# Low_Side_Drivers.net
KiCad netlist of a schematic drawn in Altium Designer
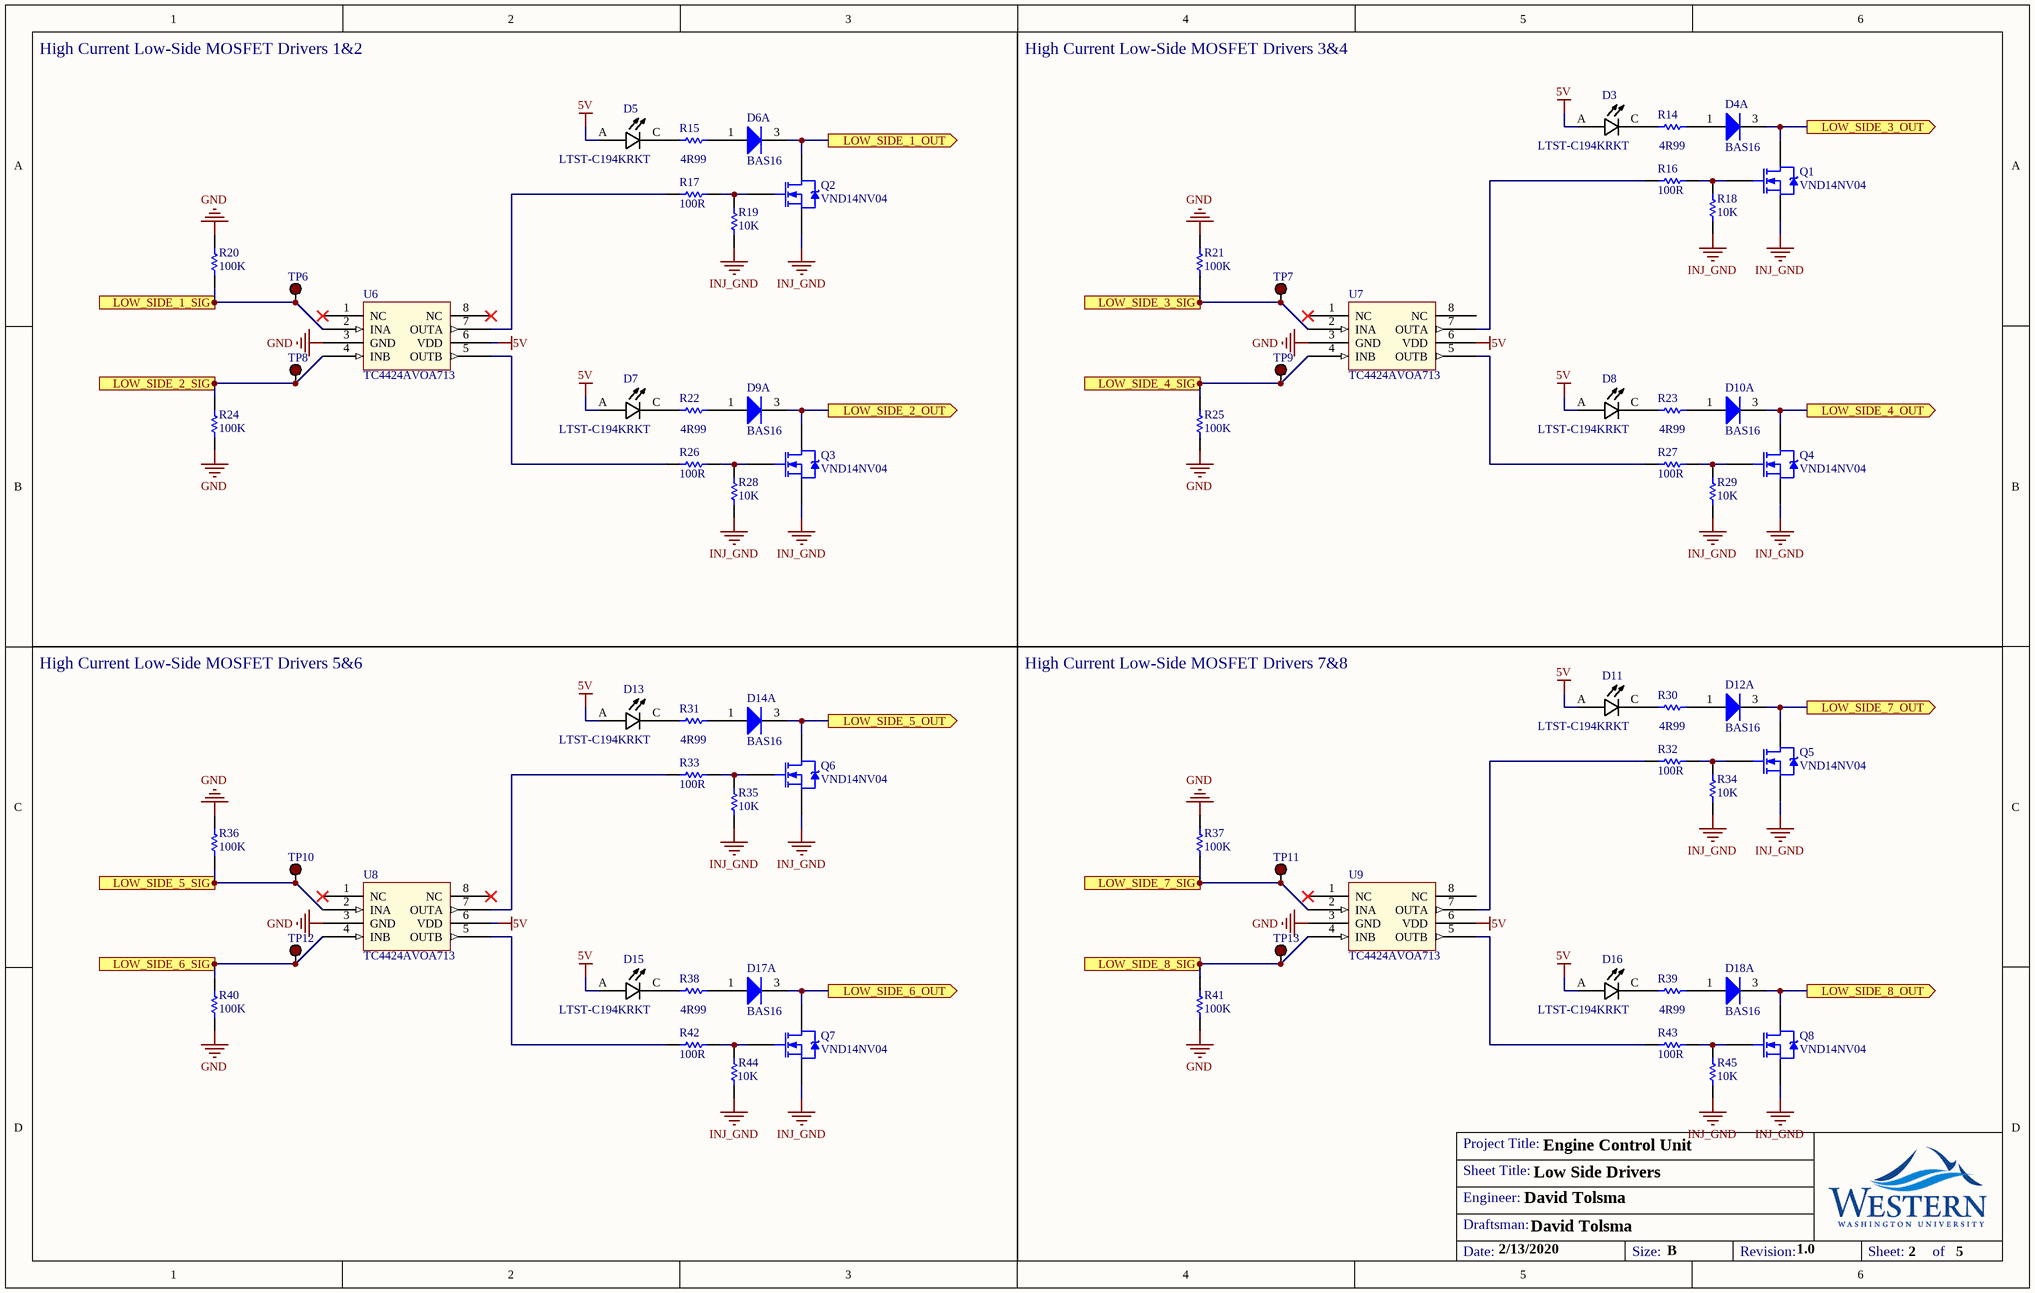
[diagram p0: Low_Side_Drivers.SchDoc]

(export (version "E")
  (design (tool "Eeschema 10.0.6"))
  (components
    (comp (ref "D3")
      (value "LTST-C194KRKT")
      (footprint "LEDC1608X35N_LTST-C194KRKT")
      (description "Red 631nm LED Indication - Discrete 2V 0603 _1608 Metric_")
      (fields (field (name "MF") "Lite-On Inc.") (field (name "DIGI-KEY_PART_NUMBER") "160-1835-1-ND"))
      (libsource (lib "ECU") (part "LTST-C194KRKT"))
    )
    (comp (ref "D4")
      (value "BAS16")
      (footprint "NXP-SOT23-3_V")
      (description "High-speed Switching Diode, 100 V, 4 ns, -65 to 150 degC, 3-Pin SOT23, RoHS, Tape and Reel")
      (fields (field (name "MANUFACTURER") "NXP Semiconductors"))
      (libsource (lib "Altium Content Vault") (part "NXP-D-A1K3-3"))
    )
    (comp (ref "D5")
      (value "LTST-C194KRKT")
      (footprint "LEDC1608X35N_LTST-C194KRKT")
      (description "Red 631nm LED Indication - Discrete 2V 0603 _1608 Metric_")
      (fields (field (name "MF") "Lite-On Inc.") (field (name "DIGI-KEY_PART_NUMBER") "160-1835-1-ND"))
      (libsource (lib "ECU") (part "LTST-C194KRKT"))
    )
    (comp (ref "D6")
      (value "BAS16")
      (footprint "NXP-SOT23-3_V")
      (description "High-speed Switching Diode, 100 V, 4 ns, -65 to 150 degC, 3-Pin SOT23, RoHS, Tape and Reel")
      (fields (field (name "MANUFACTURER") "NXP Semiconductors"))
      (libsource (lib "Altium Content Vault") (part "NXP-D-A1K3-3"))
    )
    (comp (ref "D7")
      (value "LTST-C194KRKT")
      (footprint "LEDC1608X35N_LTST-C194KRKT")
      (description "Red 631nm LED Indication - Discrete 2V 0603 _1608 Metric_")
      (fields (field (name "MF") "Lite-On Inc.") (field (name "DIGI-KEY_PART_NUMBER") "160-1835-1-ND"))
      (libsource (lib "ECU") (part "LTST-C194KRKT"))
    )
    (comp (ref "D8")
      (value "LTST-C194KRKT")
      (footprint "LEDC1608X35N_LTST-C194KRKT")
      (description "Red 631nm LED Indication - Discrete 2V 0603 _1608 Metric_")
      (fields (field (name "MF") "Lite-On Inc.") (field (name "DIGI-KEY_PART_NUMBER") "160-1835-1-ND"))
      (libsource (lib "ECU") (part "LTST-C194KRKT"))
    )
    (comp (ref "D9")
      (value "BAS16")
      (footprint "NXP-SOT23-3_V")
      (description "High-speed Switching Diode, 100 V, 4 ns, -65 to 150 degC, 3-Pin SOT23, RoHS, Tape and Reel")
      (fields (field (name "MANUFACTURER") "NXP Semiconductors"))
      (libsource (lib "Altium Content Vault") (part "NXP-D-A1K3-3"))
    )
    (comp (ref "D10")
      (value "BAS16")
      (footprint "NXP-SOT23-3_V")
      (description "High-speed Switching Diode, 100 V, 4 ns, -65 to 150 degC, 3-Pin SOT23, RoHS, Tape and Reel")
      (fields (field (name "MANUFACTURER") "NXP Semiconductors"))
      (libsource (lib "Altium Content Vault") (part "NXP-D-A1K3-3"))
    )
    (comp (ref "D11")
      (value "LTST-C194KRKT")
      (footprint "LEDC1608X35N_LTST-C194KRKT")
      (description "Red 631nm LED Indication - Discrete 2V 0603 _1608 Metric_")
      (fields (field (name "MF") "Lite-On Inc.") (field (name "DIGI-KEY_PART_NUMBER") "160-1835-1-ND"))
      (libsource (lib "ECU") (part "LTST-C194KRKT"))
    )
    (comp (ref "D12")
      (value "BAS16")
      (footprint "NXP-SOT23-3_V")
      (description "High-speed Switching Diode, 100 V, 4 ns, -65 to 150 degC, 3-Pin SOT23, RoHS, Tape and Reel")
      (fields (field (name "MANUFACTURER") "NXP Semiconductors"))
      (libsource (lib "Altium Content Vault") (part "NXP-D-A1K3-3"))
    )
    (comp (ref "D13")
      (value "LTST-C194KRKT")
      (footprint "LEDC1608X35N_LTST-C194KRKT")
      (description "Red 631nm LED Indication - Discrete 2V 0603 _1608 Metric_")
      (fields (field (name "MF") "Lite-On Inc.") (field (name "DIGI-KEY_PART_NUMBER") "160-1835-1-ND"))
      (libsource (lib "ECU") (part "LTST-C194KRKT"))
    )
    (comp (ref "D14")
      (value "BAS16")
      (footprint "NXP-SOT23-3_V")
      (description "High-speed Switching Diode, 100 V, 4 ns, -65 to 150 degC, 3-Pin SOT23, RoHS, Tape and Reel")
      (fields (field (name "MANUFACTURER") "NXP Semiconductors"))
      (libsource (lib "Altium Content Vault") (part "NXP-D-A1K3-3"))
    )
    (comp (ref "D15")
      (value "LTST-C194KRKT")
      (footprint "LEDC1608X35N_LTST-C194KRKT")
      (description "Red 631nm LED Indication - Discrete 2V 0603 _1608 Metric_")
      (fields (field (name "MF") "Lite-On Inc.") (field (name "DIGI-KEY_PART_NUMBER") "160-1835-1-ND"))
      (libsource (lib "ECU") (part "LTST-C194KRKT"))
    )
    (comp (ref "D16")
      (value "LTST-C194KRKT")
      (footprint "LEDC1608X35N_LTST-C194KRKT")
      (description "Red 631nm LED Indication - Discrete 2V 0603 _1608 Metric_")
      (fields (field (name "MF") "Lite-On Inc.") (field (name "DIGI-KEY_PART_NUMBER") "160-1835-1-ND"))
      (libsource (lib "ECU") (part "LTST-C194KRKT"))
    )
    (comp (ref "D17")
      (value "BAS16")
      (footprint "NXP-SOT23-3_V")
      (description "High-speed Switching Diode, 100 V, 4 ns, -65 to 150 degC, 3-Pin SOT23, RoHS, Tape and Reel")
      (fields (field (name "MANUFACTURER") "NXP Semiconductors"))
      (libsource (lib "Altium Content Vault") (part "NXP-D-A1K3-3"))
    )
    (comp (ref "D18")
      (value "BAS16")
      (footprint "NXP-SOT23-3_V")
      (description "High-speed Switching Diode, 100 V, 4 ns, -65 to 150 degC, 3-Pin SOT23, RoHS, Tape and Reel")
      (fields (field (name "MANUFACTURER") "NXP Semiconductors"))
      (libsource (lib "Altium Content Vault") (part "NXP-D-A1K3-3"))
    )
    (comp (ref "Q1") (value "VND14NV04") (footprint "VND14NV04") (libsource (lib "ECU") (part "VND14NV04")))
    (comp (ref "Q2") (value "VND14NV04") (footprint "VND14NV04") (libsource (lib "ECU") (part "VND14NV04")))
    (comp (ref "Q3") (value "VND14NV04") (footprint "VND14NV04") (libsource (lib "ECU") (part "VND14NV04")))
    (comp (ref "Q4") (value "VND14NV04") (footprint "VND14NV04") (libsource (lib "ECU") (part "VND14NV04")))
    (comp (ref "Q5") (value "VND14NV04") (footprint "VND14NV04") (libsource (lib "ECU") (part "VND14NV04")))
    (comp (ref "Q6") (value "VND14NV04") (footprint "VND14NV04") (libsource (lib "ECU") (part "VND14NV04")))
    (comp (ref "Q7") (value "VND14NV04") (footprint "VND14NV04") (libsource (lib "ECU") (part "VND14NV04")))
    (comp (ref "Q8") (value "VND14NV04") (footprint "VND14NV04") (libsource (lib "ECU") (part "VND14NV04")))
    (comp (ref "R14")
      (value "4R99")
      (footprint "RESC0603(1608)_M")
      (description "4R99 0.1W 1% 0603 (1608 Metric)  SMD")
      (fields (field (name "TOLERANCE") "1 %") (field (name "POWER") "0.1 W"))
      (libsource (lib "Altium Content Vault") (part "RES"))
    )
    (comp (ref "R15")
      (value "4R99")
      (footprint "RESC0603(1608)_M")
      (description "4R99 0.1W 1% 0603 (1608 Metric)  SMD")
      (fields (field (name "TOLERANCE") "1 %") (field (name "POWER") "0.1 W"))
      (libsource (lib "Altium Content Vault") (part "RES"))
    )
    (comp (ref "R16")
      (value "100R")
      (footprint "RESC1206(3216)_L")
      (description "100R 0.25W 1% 1206 (3216 Metric)  SMD")
      (fields (field (name "TOLERANCE") "1 %") (field (name "POWER") "0.25 W"))
      (libsource (lib "Altium Content Vault") (part "RES"))
    )
    (comp (ref "R17")
      (value "100R")
      (footprint "RESC1206(3216)_L")
      (description "100R 0.25W 1% 1206 (3216 Metric)  SMD")
      (fields (field (name "TOLERANCE") "1 %") (field (name "POWER") "0.25 W"))
      (libsource (lib "Altium Content Vault") (part "RES"))
    )
    (comp (ref "R18")
      (value "10K")
      (footprint "RESC0603(1608)_M")
      (description "10K 0.1W 1% 0603 (1608 Metric)  SMD")
      (fields (field (name "POWER") "0.1 W") (field (name "TOLERANCE") "1 %"))
      (libsource (lib "Altium Content Vault") (part "RES"))
    )
    (comp (ref "R19")
      (value "10K")
      (footprint "RESC0603(1608)_M")
      (description "10K 0.1W 1% 0603 (1608 Metric)  SMD")
      (fields (field (name "POWER") "0.1 W") (field (name "TOLERANCE") "1 %"))
      (libsource (lib "Altium Content Vault") (part "RES"))
    )
    (comp (ref "R20")
      (value "100K")
      (footprint "RESC0603(1608)_M")
      (description "100K 0.1W 1% 0603 (1608 Metric)  SMD")
      (fields (field (name "POWER") "0.1 W") (field (name "TOLERANCE") "1 %"))
      (libsource (lib "Altium Content Vault") (part "RES"))
    )
    (comp (ref "R21")
      (value "100K")
      (footprint "RESC0603(1608)_M")
      (description "100K 0.1W 1% 0603 (1608 Metric)  SMD")
      (fields (field (name "POWER") "0.1 W") (field (name "TOLERANCE") "1 %"))
      (libsource (lib "Altium Content Vault") (part "RES"))
    )
    (comp (ref "R22")
      (value "4R99")
      (footprint "RESC0603(1608)_M")
      (description "4R99 0.1W 1% 0603 (1608 Metric)  SMD")
      (fields (field (name "TOLERANCE") "1 %") (field (name "POWER") "0.1 W"))
      (libsource (lib "Altium Content Vault") (part "RES"))
    )
    (comp (ref "R23")
      (value "4R99")
      (footprint "RESC0603(1608)_M")
      (description "4R99 0.1W 1% 0603 (1608 Metric)  SMD")
      (fields (field (name "TOLERANCE") "1 %") (field (name "POWER") "0.1 W"))
      (libsource (lib "Altium Content Vault") (part "RES"))
    )
    (comp (ref "R24")
      (value "100K")
      (footprint "RESC0603(1608)_M")
      (description "100K 0.1W 1% 0603 (1608 Metric)  SMD")
      (fields (field (name "POWER") "0.1 W") (field (name "TOLERANCE") "1 %"))
      (libsource (lib "Altium Content Vault") (part "RES"))
    )
    (comp (ref "R25")
      (value "100K")
      (footprint "RESC0603(1608)_M")
      (description "100K 0.1W 1% 0603 (1608 Metric)  SMD")
      (fields (field (name "POWER") "0.1 W") (field (name "TOLERANCE") "1 %"))
      (libsource (lib "Altium Content Vault") (part "RES"))
    )
    (comp (ref "R26")
      (value "100R")
      (footprint "RESC1206(3216)_L")
      (description "100R 0.25W 1% 1206 (3216 Metric)  SMD")
      (fields (field (name "TOLERANCE") "1 %") (field (name "POWER") "0.25 W"))
      (libsource (lib "Altium Content Vault") (part "RES"))
    )
    (comp (ref "R27")
      (value "100R")
      (footprint "RESC1206(3216)_L")
      (description "100R 0.25W 1% 1206 (3216 Metric)  SMD")
      (fields (field (name "TOLERANCE") "1 %") (field (name "POWER") "0.25 W"))
      (libsource (lib "Altium Content Vault") (part "RES"))
    )
    (comp (ref "R28")
      (value "10K")
      (footprint "RESC0603(1608)_M")
      (description "10K 0.1W 1% 0603 (1608 Metric)  SMD")
      (fields (field (name "POWER") "0.1 W") (field (name "TOLERANCE") "1 %"))
      (libsource (lib "Altium Content Vault") (part "RES"))
    )
    (comp (ref "R29")
      (value "10K")
      (footprint "RESC0603(1608)_M")
      (description "10K 0.1W 1% 0603 (1608 Metric)  SMD")
      (fields (field (name "POWER") "0.1 W") (field (name "TOLERANCE") "1 %"))
      (libsource (lib "Altium Content Vault") (part "RES"))
    )
    (comp (ref "R30")
      (value "4R99")
      (footprint "RESC0603(1608)_M")
      (description "4R99 0.1W 1% 0603 (1608 Metric)  SMD")
      (fields (field (name "TOLERANCE") "1 %") (field (name "POWER") "0.1 W"))
      (libsource (lib "Altium Content Vault") (part "RES"))
    )
    (comp (ref "R31")
      (value "4R99")
      (footprint "RESC0603(1608)_M")
      (description "4R99 0.1W 1% 0603 (1608 Metric)  SMD")
      (fields (field (name "TOLERANCE") "1 %") (field (name "POWER") "0.1 W"))
      (libsource (lib "Altium Content Vault") (part "RES"))
    )
    (comp (ref "R32")
      (value "100R")
      (footprint "RESC1206(3216)_L")
      (description "100R 0.25W 1% 1206 (3216 Metric)  SMD")
      (fields (field (name "TOLERANCE") "1 %") (field (name "POWER") "0.25 W"))
      (libsource (lib "Altium Content Vault") (part "RES"))
    )
    (comp (ref "R33")
      (value "100R")
      (footprint "RESC1206(3216)_L")
      (description "100R 0.25W 1% 1206 (3216 Metric)  SMD")
      (fields (field (name "TOLERANCE") "1 %") (field (name "POWER") "0.25 W"))
      (libsource (lib "Altium Content Vault") (part "RES"))
    )
    (comp (ref "R34")
      (value "10K")
      (footprint "RESC0603(1608)_M")
      (description "10K 0.1W 1% 0603 (1608 Metric)  SMD")
      (fields (field (name "POWER") "0.1 W") (field (name "TOLERANCE") "1 %"))
      (libsource (lib "Altium Content Vault") (part "RES"))
    )
    (comp (ref "R35")
      (value "10K")
      (footprint "RESC0603(1608)_M")
      (description "10K 0.1W 1% 0603 (1608 Metric)  SMD")
      (fields (field (name "POWER") "0.1 W") (field (name "TOLERANCE") "1 %"))
      (libsource (lib "Altium Content Vault") (part "RES"))
    )
    (comp (ref "R36")
      (value "100K")
      (footprint "RESC0603(1608)_M")
      (description "100K 0.1W 1% 0603 (1608 Metric)  SMD")
      (fields (field (name "POWER") "0.1 W") (field (name "TOLERANCE") "1 %"))
      (libsource (lib "Altium Content Vault") (part "RES"))
    )
    (comp (ref "R37")
      (value "100K")
      (footprint "RESC0603(1608)_M")
      (description "100K 0.1W 1% 0603 (1608 Metric)  SMD")
      (fields (field (name "POWER") "0.1 W") (field (name "TOLERANCE") "1 %"))
      (libsource (lib "Altium Content Vault") (part "RES"))
    )
    (comp (ref "R38")
      (value "4R99")
      (footprint "RESC0603(1608)_M")
      (description "4R99 0.1W 1% 0603 (1608 Metric)  SMD")
      (fields (field (name "TOLERANCE") "1 %") (field (name "POWER") "0.1 W"))
      (libsource (lib "Altium Content Vault") (part "RES"))
    )
    (comp (ref "R39")
      (value "4R99")
      (footprint "RESC0603(1608)_M")
      (description "4R99 0.1W 1% 0603 (1608 Metric)  SMD")
      (fields (field (name "TOLERANCE") "1 %") (field (name "POWER") "0.1 W"))
      (libsource (lib "Altium Content Vault") (part "RES"))
    )
    (comp (ref "R40")
      (value "100K")
      (footprint "RESC0603(1608)_M")
      (description "100K 0.1W 1% 0603 (1608 Metric)  SMD")
      (fields (field (name "POWER") "0.1 W") (field (name "TOLERANCE") "1 %"))
      (libsource (lib "Altium Content Vault") (part "RES"))
    )
    (comp (ref "R41")
      (value "100K")
      (footprint "RESC0603(1608)_M")
      (description "100K 0.1W 1% 0603 (1608 Metric)  SMD")
      (fields (field (name "POWER") "0.1 W") (field (name "TOLERANCE") "1 %"))
      (libsource (lib "Altium Content Vault") (part "RES"))
    )
    (comp (ref "R42")
      (value "100R")
      (footprint "RESC1206(3216)_L")
      (description "100R 0.25W 1% 1206 (3216 Metric)  SMD")
      (fields (field (name "TOLERANCE") "1 %") (field (name "POWER") "0.25 W"))
      (libsource (lib "Altium Content Vault") (part "RES"))
    )
    (comp (ref "R43")
      (value "100R")
      (footprint "RESC1206(3216)_L")
      (description "100R 0.25W 1% 1206 (3216 Metric)  SMD")
      (fields (field (name "TOLERANCE") "1 %") (field (name "POWER") "0.25 W"))
      (libsource (lib "Altium Content Vault") (part "RES"))
    )
    (comp (ref "R44")
      (value "10K")
      (footprint "RESC0603(1608)_M")
      (description "10K 0.1W 1% 0603 (1608 Metric)  SMD")
      (fields (field (name "POWER") "0.1 W") (field (name "TOLERANCE") "1 %"))
      (libsource (lib "Altium Content Vault") (part "RES"))
    )
    (comp (ref "R45")
      (value "10K")
      (footprint "RESC0603(1608)_M")
      (description "10K 0.1W 1% 0603 (1608 Metric)  SMD")
      (fields (field (name "POWER") "0.1 W") (field (name "TOLERANCE") "1 %"))
      (libsource (lib "Altium Content Vault") (part "RES"))
    )
    (comp (ref "TP6")
      (value "5001")
      (footprint "Keystone_5001")
      (description "TEST POINT PC MINI .040\"D BLACK")
      (fields (field (name "MANUFACTURER") "Keystone Electronics"))
      (libsource (lib "WWUEE_SchematicLibrary") (part "TEST POINT"))
    )
    (comp (ref "TP7")
      (value "5001")
      (footprint "Keystone_5001")
      (description "TEST POINT PC MINI .040\"D BLACK")
      (fields (field (name "MANUFACTURER") "Keystone Electronics"))
      (libsource (lib "WWUEE_SchematicLibrary") (part "TEST POINT"))
    )
    (comp (ref "TP8")
      (value "5001")
      (footprint "Keystone_5001")
      (description "TEST POINT PC MINI .040\"D BLACK")
      (fields (field (name "MANUFACTURER") "Keystone Electronics"))
      (libsource (lib "WWUEE_SchematicLibrary") (part "TEST POINT"))
    )
    (comp (ref "TP9")
      (value "5001")
      (footprint "Keystone_5001")
      (description "TEST POINT PC MINI .040\"D BLACK")
      (fields (field (name "MANUFACTURER") "Keystone Electronics"))
      (libsource (lib "WWUEE_SchematicLibrary") (part "TEST POINT"))
    )
    (comp (ref "TP10")
      (value "5001")
      (footprint "Keystone_5001")
      (description "TEST POINT PC MINI .040\"D BLACK")
      (fields (field (name "MANUFACTURER") "Keystone Electronics"))
      (libsource (lib "WWUEE_SchematicLibrary") (part "TEST POINT"))
    )
    (comp (ref "TP11")
      (value "5001")
      (footprint "Keystone_5001")
      (description "TEST POINT PC MINI .040\"D BLACK")
      (fields (field (name "MANUFACTURER") "Keystone Electronics"))
      (libsource (lib "WWUEE_SchematicLibrary") (part "TEST POINT"))
    )
    (comp (ref "TP12")
      (value "5001")
      (footprint "Keystone_5001")
      (description "TEST POINT PC MINI .040\"D BLACK")
      (fields (field (name "MANUFACTURER") "Keystone Electronics"))
      (libsource (lib "WWUEE_SchematicLibrary") (part "TEST POINT"))
    )
    (comp (ref "TP13")
      (value "5001")
      (footprint "Keystone_5001")
      (description "TEST POINT PC MINI .040\"D BLACK")
      (fields (field (name "MANUFACTURER") "Keystone Electronics"))
      (libsource (lib "WWUEE_SchematicLibrary") (part "TEST POINT"))
    )
    (comp (ref "U6")
      (value "TC4424AVOA713")
      (footprint "TC4424AVOA713")
      (libsource (lib "ECU") (part "TC4424AVOA713"))
    )
    (comp (ref "U7")
      (value "TC4424AVOA713")
      (footprint "TC4424AVOA713")
      (libsource (lib "ECU") (part "TC4424AVOA713"))
    )
    (comp (ref "U8")
      (value "TC4424AVOA713")
      (footprint "TC4424AVOA713")
      (libsource (lib "ECU") (part "TC4424AVOA713"))
    )
    (comp (ref "U9")
      (value "TC4424AVOA713")
      (footprint "TC4424AVOA713")
      (libsource (lib "ECU") (part "TC4424AVOA713"))
    )
  )
  (nets
    (net (code "1") (name "/LOW_SIDE_1_OUT") (class "Default")
      (node (ref "D6") (pin "3") (pinfunction "K_3") (pintype "passive"))
      (node (ref "Q2") (pin "4") (pinfunction "D_4") (pintype "passive"))
    )
    (net (code "2") (name "/LOW_SIDE_1_SIG") (class "Default")
      (node (ref "R20") (pin "2") (pinfunction "2_2") (pintype "passive"))
      (node (ref "TP6") (pin "1") (pinfunction "TP_1") (pintype "passive"))
      (node (ref "U6") (pin "2") (pinfunction "INA_2") (pintype "input"))
    )
    (net (code "3") (name "/LOW_SIDE_2_OUT") (class "Default")
      (node (ref "D9") (pin "3") (pinfunction "K_3") (pintype "passive"))
      (node (ref "Q3") (pin "4") (pinfunction "D_4") (pintype "passive"))
    )
    (net (code "4") (name "/LOW_SIDE_2_SIG") (class "Default")
      (node (ref "R24") (pin "2") (pinfunction "2_2") (pintype "passive"))
      (node (ref "TP8") (pin "1") (pinfunction "TP_1") (pintype "passive"))
      (node (ref "U6") (pin "4") (pinfunction "INB_4") (pintype "input"))
    )
    (net (code "5") (name "/LOW_SIDE_3_OUT") (class "Default")
      (node (ref "D4") (pin "3") (pinfunction "K_3") (pintype "passive"))
      (node (ref "Q1") (pin "4") (pinfunction "D_4") (pintype "passive"))
    )
    (net (code "6") (name "/LOW_SIDE_3_SIG") (class "Default")
      (node (ref "R21") (pin "2") (pinfunction "2_2") (pintype "passive"))
      (node (ref "TP7") (pin "1") (pinfunction "TP_1") (pintype "passive"))
      (node (ref "U7") (pin "2") (pinfunction "INA_2") (pintype "input"))
    )
    (net (code "7") (name "/LOW_SIDE_4_OUT") (class "Default")
      (node (ref "D10") (pin "3") (pinfunction "K_3") (pintype "passive"))
      (node (ref "Q4") (pin "4") (pinfunction "D_4") (pintype "passive"))
    )
    (net (code "8") (name "/LOW_SIDE_4_SIG") (class "Default")
      (node (ref "R25") (pin "2") (pinfunction "2_2") (pintype "passive"))
      (node (ref "TP9") (pin "1") (pinfunction "TP_1") (pintype "passive"))
      (node (ref "U7") (pin "4") (pinfunction "INB_4") (pintype "input"))
    )
    (net (code "9") (name "/LOW_SIDE_5_OUT") (class "Default")
      (node (ref "D14") (pin "3") (pinfunction "K_3") (pintype "passive"))
      (node (ref "Q6") (pin "4") (pinfunction "D_4") (pintype "passive"))
    )
    (net (code "10") (name "/LOW_SIDE_5_SIG") (class "Default")
      (node (ref "R36") (pin "2") (pinfunction "2_2") (pintype "passive"))
      (node (ref "TP10") (pin "1") (pinfunction "TP_1") (pintype "passive"))
      (node (ref "U8") (pin "2") (pinfunction "INA_2") (pintype "input"))
    )
    (net (code "11") (name "/LOW_SIDE_6_OUT") (class "Default")
      (node (ref "D17") (pin "3") (pinfunction "K_3") (pintype "passive"))
      (node (ref "Q7") (pin "4") (pinfunction "D_4") (pintype "passive"))
    )
    (net (code "12") (name "/LOW_SIDE_6_SIG") (class "Default")
      (node (ref "R40") (pin "2") (pinfunction "2_2") (pintype "passive"))
      (node (ref "TP12") (pin "1") (pinfunction "TP_1") (pintype "passive"))
      (node (ref "U8") (pin "4") (pinfunction "INB_4") (pintype "input"))
    )
    (net (code "13") (name "/LOW_SIDE_7_OUT") (class "Default")
      (node (ref "D12") (pin "3") (pinfunction "K_3") (pintype "passive"))
      (node (ref "Q5") (pin "4") (pinfunction "D_4") (pintype "passive"))
    )
    (net (code "14") (name "/LOW_SIDE_7_SIG") (class "Default")
      (node (ref "R37") (pin "2") (pinfunction "2_2") (pintype "passive"))
      (node (ref "TP11") (pin "1") (pinfunction "TP_1") (pintype "passive"))
      (node (ref "U9") (pin "2") (pinfunction "INA_2") (pintype "input"))
    )
    (net (code "15") (name "/LOW_SIDE_8_OUT") (class "Default")
      (node (ref "D18") (pin "3") (pinfunction "K_3") (pintype "passive"))
      (node (ref "Q8") (pin "4") (pinfunction "D_4") (pintype "passive"))
    )
    (net (code "16") (name "/LOW_SIDE_8_SIG") (class "Default")
      (node (ref "R41") (pin "2") (pinfunction "2_2") (pintype "passive"))
      (node (ref "TP13") (pin "1") (pinfunction "TP_1") (pintype "passive"))
      (node (ref "U9") (pin "4") (pinfunction "INB_4") (pintype "input"))
    )
    (net (code "17") (name "5V") (class "Default")
      (node (ref "D11") (pin "A") (pinfunction "A_A") (pintype "passive"))
      (node (ref "D13") (pin "A") (pinfunction "A_A") (pintype "passive"))
      (node (ref "D15") (pin "A") (pinfunction "A_A") (pintype "passive"))
      (node (ref "D16") (pin "A") (pinfunction "A_A") (pintype "passive"))
      (node (ref "D3") (pin "A") (pinfunction "A_A") (pintype "passive"))
      (node (ref "D5") (pin "A") (pinfunction "A_A") (pintype "passive"))
      (node (ref "D7") (pin "A") (pinfunction "A_A") (pintype "passive"))
      (node (ref "D8") (pin "A") (pinfunction "A_A") (pintype "passive"))
      (node (ref "U6") (pin "6") (pinfunction "VDD_6") (pintype "power_in"))
      (node (ref "U7") (pin "6") (pinfunction "VDD_6") (pintype "power_in"))
      (node (ref "U8") (pin "6") (pinfunction "VDD_6") (pintype "power_in"))
      (node (ref "U9") (pin "6") (pinfunction "VDD_6") (pintype "power_in"))
    )
    (net (code "18") (name "GND") (class "Default")
      (node (ref "R20") (pin "1") (pinfunction "1_1") (pintype "passive"))
      (node (ref "R21") (pin "1") (pinfunction "1_1") (pintype "passive"))
      (node (ref "R24") (pin "1") (pinfunction "1_1") (pintype "passive"))
      (node (ref "R25") (pin "1") (pinfunction "1_1") (pintype "passive"))
      (node (ref "R36") (pin "1") (pinfunction "1_1") (pintype "passive"))
      (node (ref "R37") (pin "1") (pinfunction "1_1") (pintype "passive"))
      (node (ref "R40") (pin "1") (pinfunction "1_1") (pintype "passive"))
      (node (ref "R41") (pin "1") (pinfunction "1_1") (pintype "passive"))
      (node (ref "U6") (pin "3") (pinfunction "GND_3") (pintype "power_in"))
      (node (ref "U7") (pin "3") (pinfunction "GND_3") (pintype "power_in"))
      (node (ref "U8") (pin "3") (pinfunction "GND_3") (pintype "power_in"))
      (node (ref "U9") (pin "3") (pinfunction "GND_3") (pintype "power_in"))
    )
    (net (code "19") (name "INJ_GND") (class "Default")
      (node (ref "Q1") (pin "3") (pinfunction "S_3") (pintype "passive"))
      (node (ref "Q2") (pin "3") (pinfunction "S_3") (pintype "passive"))
      (node (ref "Q3") (pin "3") (pinfunction "S_3") (pintype "passive"))
      (node (ref "Q4") (pin "3") (pinfunction "S_3") (pintype "passive"))
      (node (ref "Q5") (pin "3") (pinfunction "S_3") (pintype "passive"))
      (node (ref "Q6") (pin "3") (pinfunction "S_3") (pintype "passive"))
      (node (ref "Q7") (pin "3") (pinfunction "S_3") (pintype "passive"))
      (node (ref "Q8") (pin "3") (pinfunction "S_3") (pintype "passive"))
      (node (ref "R18") (pin "1") (pinfunction "1_1") (pintype "passive"))
      (node (ref "R19") (pin "1") (pinfunction "1_1") (pintype "passive"))
      (node (ref "R28") (pin "1") (pinfunction "1_1") (pintype "passive"))
      (node (ref "R29") (pin "1") (pinfunction "1_1") (pintype "passive"))
      (node (ref "R34") (pin "1") (pinfunction "1_1") (pintype "passive"))
      (node (ref "R35") (pin "1") (pinfunction "1_1") (pintype "passive"))
      (node (ref "R44") (pin "1") (pinfunction "1_1") (pintype "passive"))
      (node (ref "R45") (pin "1") (pinfunction "1_1") (pintype "passive"))
    )
    (net (code "20") (name "Net-(D3-PadC)") (class "Default")
      (node (ref "D3") (pin "C") (pinfunction "C_C") (pintype "passive"))
      (node (ref "R14") (pin "1") (pinfunction "1_1") (pintype "passive"))
    )
    (net (code "21") (name "Net-(D4A-A)") (class "Default")
      (node (ref "D4") (pin "1") (pinfunction "A_1") (pintype "passive"))
      (node (ref "R14") (pin "2") (pinfunction "2_2") (pintype "passive"))
    )
    (net (code "22") (name "Net-(D5-PadC)") (class "Default")
      (node (ref "D5") (pin "C") (pinfunction "C_C") (pintype "passive"))
      (node (ref "R15") (pin "1") (pinfunction "1_1") (pintype "passive"))
    )
    (net (code "23") (name "Net-(D6A-A)") (class "Default")
      (node (ref "D6") (pin "1") (pinfunction "A_1") (pintype "passive"))
      (node (ref "R15") (pin "2") (pinfunction "2_2") (pintype "passive"))
    )
    (net (code "24") (name "Net-(D7-PadC)") (class "Default")
      (node (ref "D7") (pin "C") (pinfunction "C_C") (pintype "passive"))
      (node (ref "R22") (pin "1") (pinfunction "1_1") (pintype "passive"))
    )
    (net (code "25") (name "Net-(D8-PadC)") (class "Default")
      (node (ref "D8") (pin "C") (pinfunction "C_C") (pintype "passive"))
      (node (ref "R23") (pin "1") (pinfunction "1_1") (pintype "passive"))
    )
    (net (code "26") (name "Net-(D9A-A)") (class "Default")
      (node (ref "D9") (pin "1") (pinfunction "A_1") (pintype "passive"))
      (node (ref "R22") (pin "2") (pinfunction "2_2") (pintype "passive"))
    )
    (net (code "27") (name "Net-(D10A-A)") (class "Default")
      (node (ref "D10") (pin "1") (pinfunction "A_1") (pintype "passive"))
      (node (ref "R23") (pin "2") (pinfunction "2_2") (pintype "passive"))
    )
    (net (code "28") (name "Net-(D11-PadC)") (class "Default")
      (node (ref "D11") (pin "C") (pinfunction "C_C") (pintype "passive"))
      (node (ref "R30") (pin "1") (pinfunction "1_1") (pintype "passive"))
    )
    (net (code "29") (name "Net-(D12A-A)") (class "Default")
      (node (ref "D12") (pin "1") (pinfunction "A_1") (pintype "passive"))
      (node (ref "R30") (pin "2") (pinfunction "2_2") (pintype "passive"))
    )
    (net (code "30") (name "Net-(D13-PadC)") (class "Default")
      (node (ref "D13") (pin "C") (pinfunction "C_C") (pintype "passive"))
      (node (ref "R31") (pin "1") (pinfunction "1_1") (pintype "passive"))
    )
    (net (code "31") (name "Net-(D14A-A)") (class "Default")
      (node (ref "D14") (pin "1") (pinfunction "A_1") (pintype "passive"))
      (node (ref "R31") (pin "2") (pinfunction "2_2") (pintype "passive"))
    )
    (net (code "32") (name "Net-(D15-PadC)") (class "Default")
      (node (ref "D15") (pin "C") (pinfunction "C_C") (pintype "passive"))
      (node (ref "R38") (pin "1") (pinfunction "1_1") (pintype "passive"))
    )
    (net (code "33") (name "Net-(D16-PadC)") (class "Default")
      (node (ref "D16") (pin "C") (pinfunction "C_C") (pintype "passive"))
      (node (ref "R39") (pin "1") (pinfunction "1_1") (pintype "passive"))
    )
    (net (code "34") (name "Net-(D17A-A)") (class "Default")
      (node (ref "D17") (pin "1") (pinfunction "A_1") (pintype "passive"))
      (node (ref "R38") (pin "2") (pinfunction "2_2") (pintype "passive"))
    )
    (net (code "35") (name "Net-(D18A-A)") (class "Default")
      (node (ref "D18") (pin "1") (pinfunction "A_1") (pintype "passive"))
      (node (ref "R39") (pin "2") (pinfunction "2_2") (pintype "passive"))
    )
    (net (code "36") (name "Net-(Q1-G)") (class "Default")
      (node (ref "Q1") (pin "1") (pinfunction "G_1") (pintype "passive"))
      (node (ref "R16") (pin "2") (pinfunction "2_2") (pintype "passive"))
      (node (ref "R18") (pin "2") (pinfunction "2_2") (pintype "passive"))
    )
    (net (code "37") (name "Net-(Q2-G)") (class "Default")
      (node (ref "Q2") (pin "1") (pinfunction "G_1") (pintype "passive"))
      (node (ref "R17") (pin "2") (pinfunction "2_2") (pintype "passive"))
      (node (ref "R19") (pin "2") (pinfunction "2_2") (pintype "passive"))
    )
    (net (code "38") (name "Net-(Q3-G)") (class "Default")
      (node (ref "Q3") (pin "1") (pinfunction "G_1") (pintype "passive"))
      (node (ref "R26") (pin "2") (pinfunction "2_2") (pintype "passive"))
      (node (ref "R28") (pin "2") (pinfunction "2_2") (pintype "passive"))
    )
    (net (code "39") (name "Net-(Q4-G)") (class "Default")
      (node (ref "Q4") (pin "1") (pinfunction "G_1") (pintype "passive"))
      (node (ref "R27") (pin "2") (pinfunction "2_2") (pintype "passive"))
      (node (ref "R29") (pin "2") (pinfunction "2_2") (pintype "passive"))
    )
    (net (code "40") (name "Net-(Q5-G)") (class "Default")
      (node (ref "Q5") (pin "1") (pinfunction "G_1") (pintype "passive"))
      (node (ref "R32") (pin "2") (pinfunction "2_2") (pintype "passive"))
      (node (ref "R34") (pin "2") (pinfunction "2_2") (pintype "passive"))
    )
    (net (code "41") (name "Net-(Q6-G)") (class "Default")
      (node (ref "Q6") (pin "1") (pinfunction "G_1") (pintype "passive"))
      (node (ref "R33") (pin "2") (pinfunction "2_2") (pintype "passive"))
      (node (ref "R35") (pin "2") (pinfunction "2_2") (pintype "passive"))
    )
    (net (code "42") (name "Net-(Q7-G)") (class "Default")
      (node (ref "Q7") (pin "1") (pinfunction "G_1") (pintype "passive"))
      (node (ref "R42") (pin "2") (pinfunction "2_2") (pintype "passive"))
      (node (ref "R44") (pin "2") (pinfunction "2_2") (pintype "passive"))
    )
    (net (code "43") (name "Net-(Q8-G)") (class "Default")
      (node (ref "Q8") (pin "1") (pinfunction "G_1") (pintype "passive"))
      (node (ref "R43") (pin "2") (pinfunction "2_2") (pintype "passive"))
      (node (ref "R45") (pin "2") (pinfunction "2_2") (pintype "passive"))
    )
    (net (code "44") (name "Net-(U6-OUTA)") (class "Default")
      (node (ref "R17") (pin "1") (pinfunction "1_1") (pintype "passive"))
      (node (ref "U6") (pin "7") (pinfunction "OUTA_7") (pintype "output"))
    )
    (net (code "45") (name "Net-(U6-OUTB)") (class "Default")
      (node (ref "R26") (pin "1") (pinfunction "1_1") (pintype "passive"))
      (node (ref "U6") (pin "5") (pinfunction "OUTB_5") (pintype "output"))
    )
    (net (code "46") (name "Net-(U7-OUTA)") (class "Default")
      (node (ref "R16") (pin "1") (pinfunction "1_1") (pintype "passive"))
      (node (ref "U7") (pin "7") (pinfunction "OUTA_7") (pintype "output"))
    )
    (net (code "47") (name "Net-(U7-OUTB)") (class "Default")
      (node (ref "R27") (pin "1") (pinfunction "1_1") (pintype "passive"))
      (node (ref "U7") (pin "5") (pinfunction "OUTB_5") (pintype "output"))
    )
    (net (code "48") (name "Net-(U8-OUTA)") (class "Default")
      (node (ref "R33") (pin "1") (pinfunction "1_1") (pintype "passive"))
      (node (ref "U8") (pin "7") (pinfunction "OUTA_7") (pintype "output"))
    )
    (net (code "49") (name "Net-(U8-OUTB)") (class "Default")
      (node (ref "R42") (pin "1") (pinfunction "1_1") (pintype "passive"))
      (node (ref "U8") (pin "5") (pinfunction "OUTB_5") (pintype "output"))
    )
    (net (code "50") (name "Net-(U9-OUTA)") (class "Default")
      (node (ref "R32") (pin "1") (pinfunction "1_1") (pintype "passive"))
      (node (ref "U9") (pin "7") (pinfunction "OUTA_7") (pintype "output"))
    )
    (net (code "51") (name "Net-(U9-OUTB)") (class "Default")
      (node (ref "R43") (pin "1") (pinfunction "1_1") (pintype "passive"))
      (node (ref "U9") (pin "5") (pinfunction "OUTB_5") (pintype "output"))
    )
    (net (code "52") (name "unconnected-(U6-NC-Pad1)") (class "Default")
      (node (ref "U6") (pin "1") (pinfunction "NC_1") (pintype "tri_state+no_connect"))
    )
    (net (code "53") (name "unconnected-(U6-NC-Pad8)") (class "Default")
      (node (ref "U6") (pin "8") (pinfunction "NC_8") (pintype "tri_state+no_connect"))
    )
    (net (code "54") (name "unconnected-(U7-NC-Pad1)") (class "Default")
      (node (ref "U7") (pin "1") (pinfunction "NC_1") (pintype "tri_state+no_connect"))
    )
    (net (code "55") (name "unconnected-(U7-NC-Pad8)") (class "Default")
      (node (ref "U7") (pin "8") (pinfunction "NC_8") (pintype "tri_state"))
    )
    (net (code "56") (name "unconnected-(U8-NC-Pad1)") (class "Default")
      (node (ref "U8") (pin "1") (pinfunction "NC_1") (pintype "tri_state+no_connect"))
    )
    (net (code "57") (name "unconnected-(U8-NC-Pad8)") (class "Default")
      (node (ref "U8") (pin "8") (pinfunction "NC_8") (pintype "tri_state+no_connect"))
    )
    (net (code "58") (name "unconnected-(U9-NC-Pad1)") (class "Default")
      (node (ref "U9") (pin "1") (pinfunction "NC_1") (pintype "tri_state+no_connect"))
    )
    (net (code "59") (name "unconnected-(U9-NC-Pad8)") (class "Default")
      (node (ref "U9") (pin "8") (pinfunction "NC_8") (pintype "tri_state"))
    )
  )
)
